# Displays.net
KiCad netlist of a schematic drawn in Altium Designer
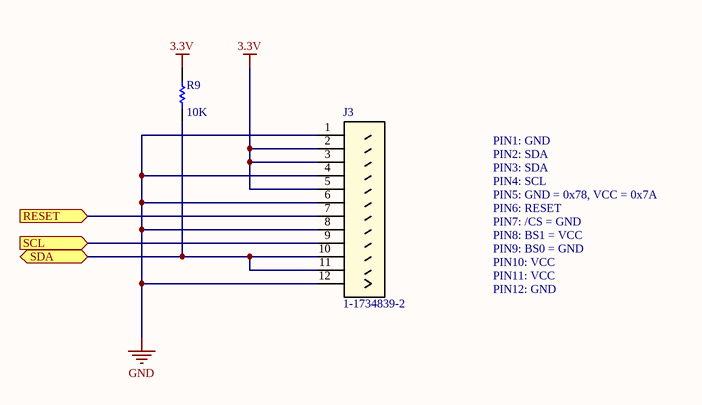
[diagram p0: Displays.SchDoc]

(export (version "E")
  (design (tool "Eeschema 10.0.6"))
  (components
    (comp (ref "J3")
      (value "1-1734839-2")
      (footprint "CONN_1-1734592-2")
      (description "Imported")
      (fields
        (field (name "RS_PART_NUMBER") "7188674")
        (field (name "COPYRIGHT") "Copyright (C) 2015 Accelerated Designs. All rights reserved")
      )
      (libsource (lib "Zif") (part "1-1734839-2"))
    )
    (comp (ref "R9")
      (value "10K")
      (footprint "6-0805_N")
      (description "Resistor")
      (fields (field (name "PUBLISHER") "Altium Limited"))
      (libsource (lib "Miscellaneous Devices") (part "Res1"))
    )
  )
  (nets
    (net (code "1") (name "/RESET") (class "Default")
      (node (ref "J3") (pin "7") (pinfunction "7_7") (pintype "passive"))
    )
    (net (code "2") (name "/SCL") (class "Default")
      (node (ref "J3") (pin "9") (pinfunction "9_9") (pintype "passive"))
    )
    (net (code "3") (name "/SDA") (class "Default")
      (node (ref "J3") (pin "10") (pinfunction "10_10") (pintype "passive"))
      (node (ref "J3") (pin "11") (pinfunction "11_11") (pintype "passive"))
      (node (ref "R9") (pin "2") (pinfunction "2_2") (pintype "passive"))
    )
    (net (code "4") (name "3.3V") (class "Default")
      (node (ref "J3") (pin "2") (pinfunction "2_2") (pintype "passive"))
      (node (ref "J3") (pin "3") (pinfunction "3_3") (pintype "passive"))
      (node (ref "J3") (pin "5") (pinfunction "5_5") (pintype "passive"))
      (node (ref "R9") (pin "1") (pinfunction "1_1") (pintype "passive"))
    )
    (net (code "5") (name "GND") (class "Default")
      (node (ref "J3") (pin "1") (pinfunction "1_1") (pintype "passive"))
      (node (ref "J3") (pin "12") (pinfunction "12_12") (pintype "passive"))
      (node (ref "J3") (pin "4") (pinfunction "4_4") (pintype "passive"))
      (node (ref "J3") (pin "6") (pinfunction "6_6") (pintype "passive"))
      (node (ref "J3") (pin "8") (pinfunction "8_8") (pintype "passive"))
    )
  )
)
